# LaserBoardv1_0.net
KiCad netlist of a schematic drawn in EAGLE
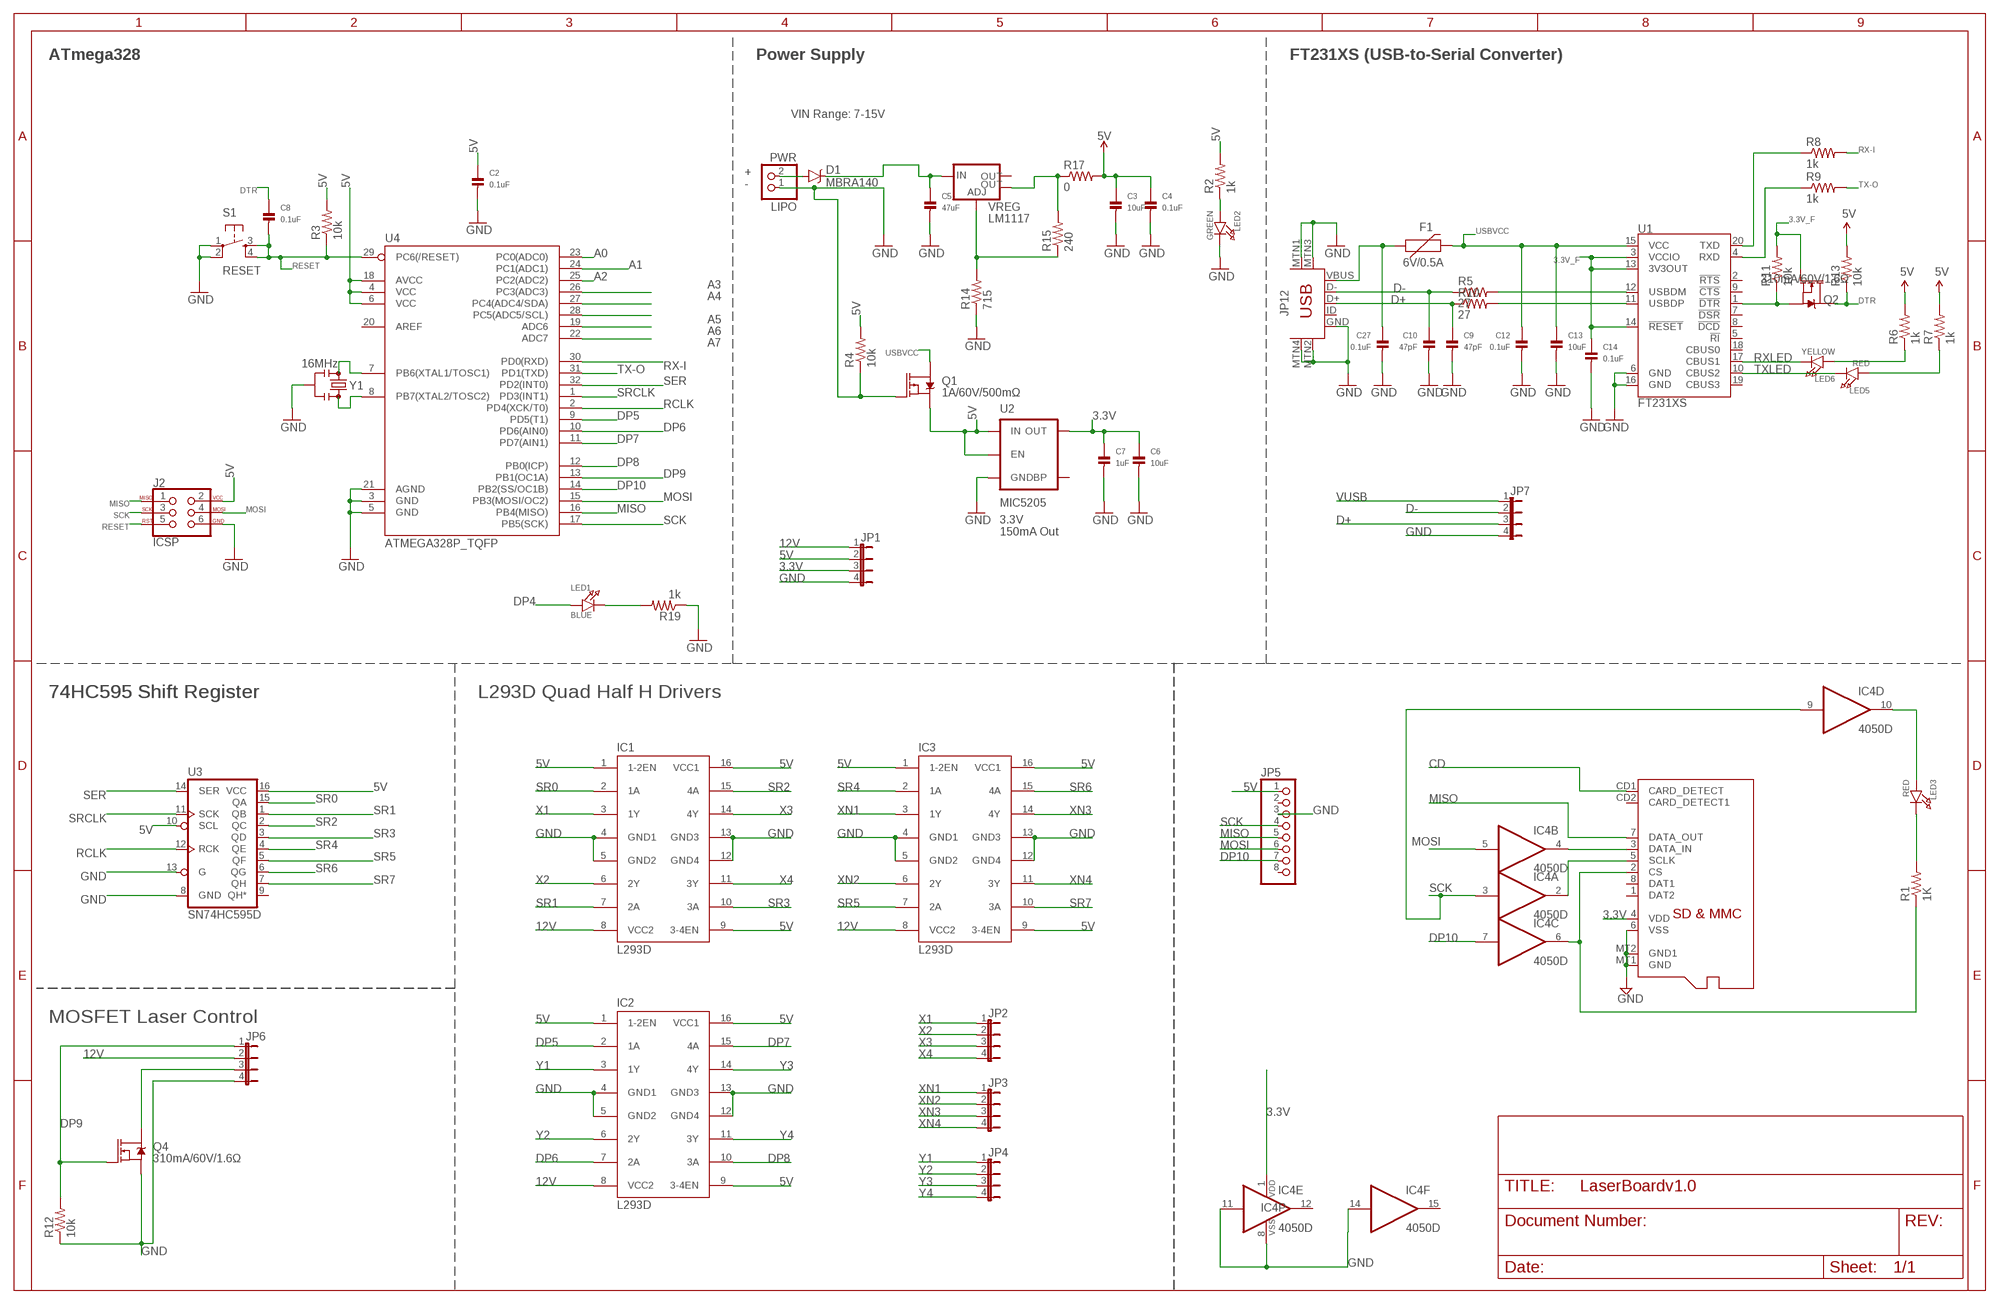
[diagram p0: schematic, sheet 1]

(export (version "E")
  (design (tool "Eeschema 10.0.6"))
  (components
    (comp (ref "C2")
      (value "0.1uF")
      (footprint "eagle-import:0805")
      (libsource (lib "eagle-import") (part "CAP_CERAMIC0805"))
    )
    (comp (ref "C3")
      (value "10uF")
      (footprint "eagle-import:0805")
      (libsource (lib "eagle-import") (part "CAP_CERAMIC0805"))
    )
    (comp (ref "C4")
      (value "0.1uF")
      (footprint "eagle-import:0805")
      (libsource (lib "eagle-import") (part "CAP_CERAMIC0805"))
    )
    (comp (ref "C5")
      (value "47uF")
      (footprint "eagle-import:0805")
      (libsource (lib "eagle-import") (part "CAP_CERAMIC0805"))
    )
    (comp (ref "C6")
      (value "10uF")
      (footprint "eagle-import:0805")
      (libsource (lib "eagle-import") (part "CAP_CERAMIC0805"))
    )
    (comp (ref "C7")
      (value "1uF")
      (footprint "eagle-import:0805")
      (libsource (lib "eagle-import") (part "CAP_CERAMIC0805"))
    )
    (comp (ref "C8")
      (value "0.1uF")
      (footprint "eagle-import:0805")
      (libsource (lib "eagle-import") (part "CAP_CERAMIC0805"))
    )
    (comp (ref "C9")
      (value "47pF")
      (footprint "eagle-import:0805")
      (libsource (lib "eagle-import") (part "CAP_CERAMIC0805"))
    )
    (comp (ref "C10")
      (value "47pF")
      (footprint "eagle-import:0805")
      (libsource (lib "eagle-import") (part "CAP_CERAMIC0805"))
    )
    (comp (ref "C12")
      (value "0.1uF")
      (footprint "eagle-import:0805")
      (libsource (lib "eagle-import") (part "CAP_CERAMIC0805"))
    )
    (comp (ref "C13")
      (value "10uF")
      (footprint "eagle-import:0805")
      (libsource (lib "eagle-import") (part "CAP_CERAMIC0805"))
    )
    (comp (ref "C14")
      (value "0.1uF")
      (footprint "eagle-import:0805")
      (libsource (lib "eagle-import") (part "CAP_CERAMIC0805"))
    )
    (comp (ref "C27")
      (value "0.1uF")
      (footprint "eagle-import:0805")
      (libsource (lib "eagle-import") (part "CAP_CERAMIC0805"))
    )
    (comp (ref "D1")
      (value "MBRA140")
      (footprint "eagle-import:SMA-DIODE")
      (libsource (lib "eagle-import") (part "MBRA140"))
    )
    (comp (ref "F1")
      (value "6V/0.5A")
      (footprint "eagle-import:1206")
      (libsource (lib "eagle-import") (part "PTC-HALF_AMP"))
    )
    (comp (ref "IC1")
      (value "L293D")
      (footprint "eagle-import:DIL16")
      (fields (field (name "MF") "STMicroelectronics"))
      (libsource (lib "eagle-import") (part "L293D"))
    )
    (comp (ref "IC2")
      (value "L293D")
      (footprint "eagle-import:DIL16")
      (fields (field (name "MF") "STMicroelectronics"))
      (libsource (lib "eagle-import") (part "L293D"))
    )
    (comp (ref "IC3")
      (value "L293D")
      (footprint "eagle-import:DIL16")
      (fields (field (name "MF") "STMicroelectronics"))
      (libsource (lib "eagle-import") (part "L293D"))
    )
    (comp (ref "IC4")
      (value "4050D")
      (footprint "eagle-import:SO16")
      (libsource (lib "eagle-import") (part "4050D"))
    )
    (comp (ref "J2")
      (value "ICSP")
      (footprint "eagle-import:2X3")
      (libsource (lib "eagle-import") (part "AVR_SPI_PROG_3X2PTH"))
    )
    (comp (ref "JP1")
      (value "JP4E")
      (footprint "eagle-import:JP4")
      (libsource (lib "eagle-import") (part "JP4E"))
    )
    (comp (ref "JP2")
      (value "JP4E")
      (footprint "eagle-import:JP4")
      (libsource (lib "eagle-import") (part "JP4E"))
    )
    (comp (ref "JP3")
      (value "JP4E")
      (footprint "eagle-import:JP4")
      (libsource (lib "eagle-import") (part "JP4E"))
    )
    (comp (ref "JP4")
      (value "JP4E")
      (footprint "eagle-import:JP4")
      (libsource (lib "eagle-import") (part "JP4E"))
    )
    (comp (ref "JP5")
      (value "PINHD-1X8BIG")
      (footprint "eagle-import:1X08-BIG")
      (libsource (lib "eagle-import") (part "PINHD-1X8BIG"))
    )
    (comp (ref "JP6")
      (value "JP4E")
      (footprint "eagle-import:JP4")
      (libsource (lib "eagle-import") (part "JP4E"))
    )
    (comp (ref "JP7")
      (value "JP4E")
      (footprint "eagle-import:JP4")
      (libsource (lib "eagle-import") (part "JP4E"))
    )
    (comp (ref "JP12")
      (value "USB-MINIB-5PIN")
      (footprint "eagle-import:USB-MINIB")
      (libsource (lib "eagle-import") (part "USB-MINIB-5PIN"))
    )
    (comp (ref "LED1")
      (value "BLUE")
      (footprint "eagle-import:CHIPLED_0805")
      (libsource (lib "eagle-import") (part "LED0805"))
    )
    (comp (ref "LED2")
      (value "GREEN")
      (footprint "eagle-import:CHIPLED_0805")
      (libsource (lib "eagle-import") (part "LED0805"))
    )
    (comp (ref "LED3")
      (value "RED")
      (footprint "eagle-import:CHIPLED_0805")
      (libsource (lib "eagle-import") (part "LED0805"))
    )
    (comp (ref "LED5")
      (value "RED")
      (footprint "eagle-import:CHIPLED_0805")
      (libsource (lib "eagle-import") (part "LED0805"))
    )
    (comp (ref "LED6")
      (value "YELLOW")
      (footprint "eagle-import:CHIPLED_0805")
      (libsource (lib "eagle-import") (part "LED0805"))
    )
    (comp (ref "PWR")
      (value "LIPO")
      (footprint "eagle-import:JST-PH-2-THM-RA")
      (libsource (lib "eagle-import") (part "JST_2PIN-THM-RA"))
    )
    (comp (ref "Q1")
      (value "1A/60V/500mΩ")
      (footprint "eagle-import:SOT23-3")
      (libsource (lib "eagle-import") (part "MOSFET-PCH-ZXMP6A13F"))
    )
    (comp (ref "Q2")
      (value "310mA/60V/1.6Ω")
      (footprint "eagle-import:SOT323")
      (libsource (lib "eagle-import") (part "MOSFET-NCH-2N7002PW"))
    )
    (comp (ref "Q4")
      (value "310mA/60V/1.6Ω")
      (footprint "eagle-import:SOT323")
      (libsource (lib "eagle-import") (part "SparkFun-DiscreteSemi_514_MOSFET-NCH-2N7002PW"))
    )
    (comp (ref "R1")
      (value "1K")
      (footprint "eagle-import:R0805")
      (libsource (lib "eagle-import") (part "R-US_R0805"))
    )
    (comp (ref "R2")
      (value "1k")
      (footprint "eagle-import:R0805")
      (libsource (lib "eagle-import") (part "R-US_R0805"))
    )
    (comp (ref "R3")
      (value "10k")
      (footprint "eagle-import:R0805")
      (libsource (lib "eagle-import") (part "R-US_R0805"))
    )
    (comp (ref "R4")
      (value "10k")
      (footprint "eagle-import:R0805")
      (libsource (lib "eagle-import") (part "R-US_R0805"))
    )
    (comp (ref "R5")
      (value "27")
      (footprint "eagle-import:R0805")
      (libsource (lib "eagle-import") (part "R-US_R0805"))
    )
    (comp (ref "R6")
      (value "1k")
      (footprint "eagle-import:R0805")
      (libsource (lib "eagle-import") (part "R-US_R0805"))
    )
    (comp (ref "R7")
      (value "1k")
      (footprint "eagle-import:R0805")
      (libsource (lib "eagle-import") (part "R-US_R0805"))
    )
    (comp (ref "R8")
      (value "1k")
      (footprint "eagle-import:R0805")
      (libsource (lib "eagle-import") (part "R-US_R0805"))
    )
    (comp (ref "R9")
      (value "1k")
      (footprint "eagle-import:R0805")
      (libsource (lib "eagle-import") (part "R-US_R0805"))
    )
    (comp (ref "R10")
      (value "27")
      (footprint "eagle-import:R0805")
      (libsource (lib "eagle-import") (part "R-US_R0805"))
    )
    (comp (ref "R11")
      (value "10k")
      (footprint "eagle-import:R0805")
      (libsource (lib "eagle-import") (part "R-US_R0805"))
    )
    (comp (ref "R12")
      (value "10k")
      (footprint "eagle-import:R0805")
      (libsource (lib "eagle-import") (part "R-US_R0805"))
    )
    (comp (ref "R13")
      (value "10k")
      (footprint "eagle-import:R0805")
      (libsource (lib "eagle-import") (part "R-US_R0805"))
    )
    (comp (ref "R14")
      (value "715")
      (footprint "eagle-import:R0805")
      (libsource (lib "eagle-import") (part "R-US_R0805"))
    )
    (comp (ref "R15")
      (value "240")
      (footprint "eagle-import:R0805")
      (libsource (lib "eagle-import") (part "R-US_R0805"))
    )
    (comp (ref "R17")
      (value "0")
      (footprint "eagle-import:R0805")
      (libsource (lib "eagle-import") (part "R-US_R0805"))
    )
    (comp (ref "R19")
      (value "1k")
      (footprint "eagle-import:R0805")
      (libsource (lib "eagle-import") (part "R-US_R0805"))
    )
    (comp (ref "S1")
      (value "RESET")
      (footprint "eagle-import:TACTILE_SWITCH_SMD_4.6X2.8MM")
      (libsource (lib "eagle-import") (part "SWITCH_SPST_4_PINRECT"))
    )
    (comp (ref "U1")
      (value "FT231XS")
      (footprint "eagle-import:SSOP20_L")
      (libsource (lib "eagle-import") (part "FT231XS"))
    )
    (comp (ref "U2")
      (value "MIC5205")
      (footprint "eagle-import:SOT23-5")
      (libsource (lib "eagle-import") (part "MIC52053.3V"))
    )
    (comp (ref "U3")
      (value "SN74HC595D")
      (footprint "eagle-import:SO16")
      (libsource (lib "eagle-import") (part "74595DHC"))
    )
    (comp (ref "U4")
      (value "ATMEGA328P_TQFP")
      (footprint "eagle-import:TQFP32-08")
      (libsource (lib "eagle-import") (part "ATMEGA328P_TQFP"))
    )
    (comp (ref "VREG")
      (value "LM1117")
      (footprint "eagle-import:SOT223")
      (libsource (lib "eagle-import") (part "V_REG_LM1117SOT223"))
    )
    (comp (ref "X1")
      (value "MICROSD")
      (footprint "eagle-import:MICROSD")
      (libsource (lib "eagle-import") (part "MICROSD"))
    )
    (comp (ref "Y1")
      (value "16MHz")
      (footprint "eagle-import:RESONATOR-SMD-3.2X1.3")
      (libsource (lib "eagle-import") (part "RESONATOR-16MHZSMD_3.2X1.3"))
    )
  )
  (nets
    (net (code "1") (name "/3.3V") (class "Default")
      (node (ref "C6") (pin "1") (pinfunction "P$1_1") (pintype "passive"))
      (node (ref "C7") (pin "1") (pinfunction "P$1_1") (pintype "passive"))
      (node (ref "IC4") (pin "1") (pinfunction "VDD_1") (pintype "power_in"))
      (node (ref "JP1") (pin "3") (pinfunction "3_3") (pintype "passive"))
      (node (ref "U2") (pin "5") (pinfunction "OUT_5") (pintype "passive"))
      (node (ref "X1") (pin "4") (pinfunction "VDD_4") (pintype "power_in"))
    )
    (net (code "2") (name "/12V") (class "Default")
      (node (ref "C5") (pin "1") (pinfunction "P$1_1") (pintype "passive"))
      (node (ref "D1") (pin "C") (pinfunction "C_C") (pintype "passive"))
      (node (ref "IC1") (pin "8") (pinfunction "VCC2_8") (pintype "power_in"))
      (node (ref "IC2") (pin "8") (pinfunction "VCC2_8") (pintype "power_in"))
      (node (ref "IC3") (pin "8") (pinfunction "VCC2_8") (pintype "power_in"))
      (node (ref "JP1") (pin "1") (pinfunction "1_1") (pintype "passive"))
      (node (ref "JP6") (pin "2") (pinfunction "2_2") (pintype "passive"))
      (node (ref "VREG") (pin "3") (pinfunction "IN_3") (pintype "input"))
    )
    (net (code "3") (name "/CD") (class "Default")
      (node (ref "X1") (pin "CD1") (pinfunction "CARD_DETECT_CD1") (pintype "passive"))
    )
    (net (code "4") (name "/D+") (class "Default")
      (node (ref "C9") (pin "1") (pinfunction "P$1_1") (pintype "passive"))
      (node (ref "JP12") (pin "D+") (pinfunction "D+_D+") (pintype "bidirectional"))
      (node (ref "JP7") (pin "3") (pinfunction "3_3") (pintype "passive"))
      (node (ref "R10") (pin "1") (pinfunction "1_1") (pintype "passive"))
    )
    (net (code "5") (name "/D-") (class "Default")
      (node (ref "C10") (pin "1") (pinfunction "P$1_1") (pintype "passive"))
      (node (ref "JP12") (pin "D-") (pinfunction "D-_D-") (pintype "bidirectional"))
      (node (ref "JP7") (pin "2") (pinfunction "2_2") (pintype "passive"))
      (node (ref "R5") (pin "1") (pinfunction "1_1") (pintype "passive"))
    )
    (net (code "6") (name "/RXLED") (class "Default")
      (node (ref "LED6") (pin "C") (pinfunction "C_C") (pintype "passive"))
      (node (ref "U1") (pin "17") (pinfunction "CBUS1_17") (pintype "bidirectional"))
    )
    (net (code "7") (name "/TXLED") (class "Default")
      (node (ref "LED5") (pin "C") (pinfunction "C_C") (pintype "passive"))
      (node (ref "U1") (pin "10") (pinfunction "CBUS2_10") (pintype "bidirectional"))
    )
    (net (code "8") (name "/VUSB") (class "Default")
      (node (ref "C27") (pin "1") (pinfunction "P$1_1") (pintype "passive"))
      (node (ref "F1") (pin "1") (pinfunction "1_1") (pintype "bidirectional"))
      (node (ref "JP12") (pin "VBUS") (pinfunction "VBUS_VBUS") (pintype "bidirectional"))
      (node (ref "JP7") (pin "1") (pinfunction "1_1") (pintype "passive"))
    )
    (net (code "9") (name "/X1") (class "Default")
      (node (ref "IC1") (pin "3") (pinfunction "1Y_3") (pintype "output"))
      (node (ref "JP2") (pin "1") (pinfunction "1_1") (pintype "passive"))
    )
    (net (code "10") (name "/X2") (class "Default")
      (node (ref "IC1") (pin "6") (pinfunction "2Y_6") (pintype "output"))
      (node (ref "JP2") (pin "2") (pinfunction "2_2") (pintype "passive"))
    )
    (net (code "11") (name "/X3") (class "Default")
      (node (ref "IC1") (pin "14") (pinfunction "4Y_14") (pintype "output"))
      (node (ref "JP2") (pin "3") (pinfunction "3_3") (pintype "passive"))
    )
    (net (code "12") (name "/X4") (class "Default")
      (node (ref "IC1") (pin "11") (pinfunction "3Y_11") (pintype "output"))
      (node (ref "JP2") (pin "4") (pinfunction "4_4") (pintype "passive"))
    )
    (net (code "13") (name "/XN1") (class "Default")
      (node (ref "IC3") (pin "3") (pinfunction "1Y_3") (pintype "output"))
      (node (ref "JP3") (pin "1") (pinfunction "1_1") (pintype "passive"))
    )
    (net (code "14") (name "/XN2") (class "Default")
      (node (ref "IC3") (pin "6") (pinfunction "2Y_6") (pintype "output"))
      (node (ref "JP3") (pin "2") (pinfunction "2_2") (pintype "passive"))
    )
    (net (code "15") (name "/XN3") (class "Default")
      (node (ref "IC3") (pin "14") (pinfunction "4Y_14") (pintype "output"))
      (node (ref "JP3") (pin "3") (pinfunction "3_3") (pintype "passive"))
    )
    (net (code "16") (name "/XN4") (class "Default")
      (node (ref "IC3") (pin "11") (pinfunction "3Y_11") (pintype "output"))
      (node (ref "JP3") (pin "4") (pinfunction "4_4") (pintype "passive"))
    )
    (net (code "17") (name "/Y1") (class "Default")
      (node (ref "IC2") (pin "3") (pinfunction "1Y_3") (pintype "output"))
      (node (ref "JP4") (pin "1") (pinfunction "1_1") (pintype "passive"))
    )
    (net (code "18") (name "/Y2") (class "Default")
      (node (ref "IC2") (pin "6") (pinfunction "2Y_6") (pintype "output"))
      (node (ref "JP4") (pin "2") (pinfunction "2_2") (pintype "passive"))
    )
    (net (code "19") (name "/Y3") (class "Default")
      (node (ref "IC2") (pin "14") (pinfunction "4Y_14") (pintype "output"))
      (node (ref "JP4") (pin "3") (pinfunction "3_3") (pintype "passive"))
    )
    (net (code "20") (name "/Y4") (class "Default")
      (node (ref "IC2") (pin "11") (pinfunction "3Y_11") (pintype "output"))
      (node (ref "JP4") (pin "4") (pinfunction "4_4") (pintype "passive"))
    )
    (net (code "21") (name "3.3V_F") (class "Default")
      (node (ref "C14") (pin "1") (pinfunction "P$1_1") (pintype "passive"))
      (node (ref "Q2") (pin "1") (pinfunction "G_1") (pintype "bidirectional"))
      (node (ref "R11") (pin "2") (pinfunction "2_2") (pintype "passive"))
      (node (ref "U1") (pin "13") (pinfunction "3V3OUT_13") (pintype "bidirectional"))
      (node (ref "U1") (pin "14") (pinfunction "~{RESET}_14") (pintype "bidirectional"))
      (node (ref "U1") (pin "3") (pinfunction "VCCIO_3") (pintype "bidirectional"))
    )
    (net (code "22") (name "5V") (class "Default")
      (node (ref "C2") (pin "1") (pinfunction "P$1_1") (pintype "passive"))
      (node (ref "C3") (pin "1") (pinfunction "P$1_1") (pintype "passive"))
      (node (ref "C4") (pin "1") (pinfunction "P$1_1") (pintype "passive"))
      (node (ref "IC1") (pin "1") (pinfunction "1-2EN_1") (pintype "input"))
      (node (ref "IC1") (pin "16") (pinfunction "VCC1_16") (pintype "power_in"))
      (node (ref "IC1") (pin "9") (pinfunction "3-4EN_9") (pintype "input"))
      (node (ref "IC2") (pin "1") (pinfunction "1-2EN_1") (pintype "input"))
      (node (ref "IC2") (pin "16") (pinfunction "VCC1_16") (pintype "power_in"))
      (node (ref "IC2") (pin "9") (pinfunction "3-4EN_9") (pintype "input"))
      (node (ref "IC3") (pin "1") (pinfunction "1-2EN_1") (pintype "input"))
      (node (ref "IC3") (pin "16") (pinfunction "VCC1_16") (pintype "power_in"))
      (node (ref "IC3") (pin "9") (pinfunction "3-4EN_9") (pintype "input"))
      (node (ref "J2") (pin "2") (pinfunction "2_2") (pintype "passive"))
      (node (ref "JP1") (pin "2") (pinfunction "2_2") (pintype "passive"))
      (node (ref "JP5") (pin "1") (pinfunction "1_1") (pintype "passive"))
      (node (ref "Q1") (pin "2") (pinfunction "S_2") (pintype "bidirectional"))
      (node (ref "R13") (pin "2") (pinfunction "2_2") (pintype "passive"))
      (node (ref "R17") (pin "2") (pinfunction "2_2") (pintype "passive"))
      (node (ref "R2") (pin "2") (pinfunction "2_2") (pintype "passive"))
      (node (ref "R3") (pin "2") (pinfunction "2_2") (pintype "passive"))
      (node (ref "R4") (pin "2") (pinfunction "2_2") (pintype "passive"))
      (node (ref "R6") (pin "2") (pinfunction "2_2") (pintype "passive"))
      (node (ref "R7") (pin "2") (pinfunction "2_2") (pintype "passive"))
      (node (ref "U2") (pin "1") (pinfunction "IN_1") (pintype "input"))
      (node (ref "U2") (pin "3") (pinfunction "EN_3") (pintype "input"))
      (node (ref "U3") (pin "10") (pinfunction "SCL_10") (pintype "input"))
      (node (ref "U3") (pin "16") (pinfunction "VCC_16") (pintype "power_in"))
      (node (ref "U4") (pin "18") (pinfunction "AVCC_18") (pintype "bidirectional"))
      (node (ref "U4") (pin "4") (pinfunction "VCC_4") (pintype "bidirectional"))
      (node (ref "U4") (pin "6") (pinfunction "VCC_6") (pintype "bidirectional"))
    )
    (net (code "23") (name "A0") (class "Default")
      (node (ref "U4") (pin "23") (pinfunction "PC0(ADC0)_23") (pintype "bidirectional"))
    )
    (net (code "24") (name "A1") (class "Default")
      (node (ref "U4") (pin "24") (pinfunction "PC1(ADC1)_24") (pintype "bidirectional"))
    )
    (net (code "25") (name "A2") (class "Default")
      (node (ref "U4") (pin "25") (pinfunction "PC2(ADC2)_25") (pintype "bidirectional"))
    )
    (net (code "26") (name "DP4") (class "Default")
      (node (ref "LED1") (pin "A") (pinfunction "A_A") (pintype "passive"))
    )
    (net (code "27") (name "DP5") (class "Default")
      (node (ref "IC2") (pin "2") (pinfunction "1A_2") (pintype "input"))
      (node (ref "U4") (pin "9") (pinfunction "PD5(T1)_9") (pintype "bidirectional"))
    )
    (net (code "28") (name "DP6") (class "Default")
      (node (ref "IC2") (pin "7") (pinfunction "2A_7") (pintype "input"))
      (node (ref "U4") (pin "10") (pinfunction "PD6(AIN0)_10") (pintype "bidirectional"))
    )
    (net (code "29") (name "DP7") (class "Default")
      (node (ref "IC2") (pin "15") (pinfunction "4A_15") (pintype "input"))
      (node (ref "U4") (pin "11") (pinfunction "PD7(AIN1)_11") (pintype "bidirectional"))
    )
    (net (code "30") (name "DP8") (class "Default")
      (node (ref "IC2") (pin "10") (pinfunction "3A_10") (pintype "input"))
      (node (ref "U4") (pin "12") (pinfunction "PB0(ICP)_12") (pintype "bidirectional"))
    )
    (net (code "31") (name "DP9") (class "Default")
      (node (ref "JP6") (pin "1") (pinfunction "1_1") (pintype "passive"))
      (node (ref "Q4") (pin "1") (pinfunction "G_1") (pintype "bidirectional"))
      (node (ref "R12") (pin "2") (pinfunction "2_2") (pintype "passive"))
      (node (ref "U4") (pin "13") (pinfunction "PB1(OC1A)_13") (pintype "bidirectional"))
    )
    (net (code "32") (name "DP10") (class "Default")
      (node (ref "IC4") (pin "7") (pinfunction "I_7") (pintype "input"))
      (node (ref "JP5") (pin "7") (pinfunction "7_7") (pintype "passive"))
      (node (ref "U4") (pin "14") (pinfunction "PB2(SS/OC1B)_14") (pintype "bidirectional"))
    )
    (net (code "33") (name "DTR") (class "Default")
      (node (ref "C8") (pin "1") (pinfunction "P$1_1") (pintype "passive"))
      (node (ref "Q2") (pin "3") (pinfunction "D_3") (pintype "bidirectional"))
      (node (ref "R13") (pin "1") (pinfunction "1_1") (pintype "passive"))
    )
    (net (code "34") (name "GND") (class "Default")
      (node (ref "C10") (pin "2") (pinfunction "P$2_2") (pintype "passive"))
      (node (ref "C12") (pin "2") (pinfunction "P$2_2") (pintype "passive"))
      (node (ref "C13") (pin "2") (pinfunction "P$2_2") (pintype "passive"))
      (node (ref "C14") (pin "2") (pinfunction "P$2_2") (pintype "passive"))
      (node (ref "C2") (pin "2") (pinfunction "P$2_2") (pintype "passive"))
      (node (ref "C27") (pin "2") (pinfunction "P$2_2") (pintype "passive"))
      (node (ref "C3") (pin "2") (pinfunction "P$2_2") (pintype "passive"))
      (node (ref "C4") (pin "2") (pinfunction "P$2_2") (pintype "passive"))
      (node (ref "C5") (pin "2") (pinfunction "P$2_2") (pintype "passive"))
      (node (ref "C6") (pin "2") (pinfunction "P$2_2") (pintype "passive"))
      (node (ref "C7") (pin "2") (pinfunction "P$2_2") (pintype "passive"))
      (node (ref "C9") (pin "2") (pinfunction "P$2_2") (pintype "passive"))
      (node (ref "IC1") (pin "12") (pinfunction "GND4_12") (pintype "power_in"))
      (node (ref "IC1") (pin "13") (pinfunction "GND3_13") (pintype "power_in"))
      (node (ref "IC1") (pin "4") (pinfunction "GND1_4") (pintype "power_in"))
      (node (ref "IC1") (pin "5") (pinfunction "GND2_5") (pintype "power_in"))
      (node (ref "IC2") (pin "12") (pinfunction "GND4_12") (pintype "power_in"))
      (node (ref "IC2") (pin "13") (pinfunction "GND3_13") (pintype "power_in"))
      (node (ref "IC2") (pin "4") (pinfunction "GND1_4") (pintype "power_in"))
      (node (ref "IC2") (pin "5") (pinfunction "GND2_5") (pintype "power_in"))
      (node (ref "IC3") (pin "12") (pinfunction "GND4_12") (pintype "power_in"))
      (node (ref "IC3") (pin "13") (pinfunction "GND3_13") (pintype "power_in"))
      (node (ref "IC3") (pin "4") (pinfunction "GND1_4") (pintype "power_in"))
      (node (ref "IC3") (pin "5") (pinfunction "GND2_5") (pintype "power_in"))
      (node (ref "IC4") (pin "11") (pinfunction "I_11") (pintype "input"))
      (node (ref "IC4") (pin "14") (pinfunction "I_14") (pintype "input"))
      (node (ref "IC4") (pin "8") (pinfunction "VSS_8") (pintype "power_in"))
      (node (ref "J2") (pin "6") (pinfunction "6_6") (pintype "passive"))
      (node (ref "JP1") (pin "4") (pinfunction "4_4") (pintype "passive"))
      (node (ref "JP12") (pin "GND") (pinfunction "GND_GND") (pintype "bidirectional"))
      (node (ref "JP12") (pin "MTN1") (pinfunction "MTN2_MTN1") (pintype "bidirectional"))
      (node (ref "JP12") (pin "MTN2") (pinfunction "MTN3_MTN2") (pintype "bidirectional"))
      (node (ref "JP12") (pin "MTN3") (pinfunction "MTN1_MTN3") (pintype "bidirectional"))
      (node (ref "JP12") (pin "MTN4") (pinfunction "MTN4_MTN4") (pintype "bidirectional"))
      (node (ref "JP5") (pin "3") (pinfunction "3_3") (pintype "passive"))
      (node (ref "JP6") (pin "4") (pinfunction "4_4") (pintype "passive"))
      (node (ref "JP7") (pin "4") (pinfunction "4_4") (pintype "passive"))
      (node (ref "LED2") (pin "C") (pinfunction "C_C") (pintype "passive"))
      (node (ref "PWR") (pin "1") (pinfunction "2_1") (pintype "passive"))
      (node (ref "Q1") (pin "1") (pinfunction "G_1") (pintype "bidirectional"))
      (node (ref "Q4") (pin "2") (pinfunction "S_2") (pintype "bidirectional"))
      (node (ref "R12") (pin "1") (pinfunction "1_1") (pintype "passive"))
      (node (ref "R14") (pin "1") (pinfunction "1_1") (pintype "passive"))
      (node (ref "R19") (pin "1") (pinfunction "1_1") (pintype "passive"))
      (node (ref "R4") (pin "1") (pinfunction "1_1") (pintype "passive"))
      (node (ref "S1") (pin "1") (pinfunction "1_1") (pintype "passive"))
      (node (ref "S1") (pin "2") (pinfunction "2_2") (pintype "passive"))
      (node (ref "U1") (pin "16") (pinfunction "GND_16") (pintype "bidirectional"))
      (node (ref "U1") (pin "6") (pinfunction "GND_6") (pintype "bidirectional"))
      (node (ref "U2") (pin "2") (pinfunction "GND_2") (pintype "input"))
      (node (ref "U3") (pin "13") (pinfunction "G_13") (pintype "input"))
      (node (ref "U3") (pin "8") (pinfunction "GND_8") (pintype "power_in"))
      (node (ref "U4") (pin "21") (pinfunction "AGND_21") (pintype "bidirectional"))
      (node (ref "U4") (pin "3") (pinfunction "GND_3") (pintype "bidirectional"))
      (node (ref "U4") (pin "5") (pinfunction "GND_5") (pintype "bidirectional"))
      (node (ref "X1") (pin "6") (pinfunction "VSS_6") (pintype "power_in"))
      (node (ref "X1") (pin "MT1") (pinfunction "GND_MT1") (pintype "power_in"))
      (node (ref "X1") (pin "MT2") (pinfunction "GND1_MT2") (pintype "power_in"))
      (node (ref "Y1") (pin "2") (pinfunction "2_2") (pintype "passive"))
    )
    (net (code "35") (name "MISO") (class "Default")
      (node (ref "J2") (pin "1") (pinfunction "1_1") (pintype "passive"))
      (node (ref "JP5") (pin "5") (pinfunction "5_5") (pintype "passive"))
      (node (ref "U4") (pin "16") (pinfunction "PB4(MISO)_16") (pintype "bidirectional"))
      (node (ref "X1") (pin "7") (pinfunction "DATA_OUT_7") (pintype "output"))
    )
    (net (code "36") (name "MOSI") (class "Default")
      (node (ref "IC4") (pin "5") (pinfunction "I_5") (pintype "input"))
      (node (ref "J2") (pin "4") (pinfunction "4_4") (pintype "passive"))
      (node (ref "JP5") (pin "6") (pinfunction "6_6") (pintype "passive"))
      (node (ref "U4") (pin "15") (pinfunction "PB3(MOSI/OC2)_15") (pintype "bidirectional"))
    )
    (net (code "37") (name "Net-(IC4A-O)") (class "Default")
      (node (ref "IC4") (pin "2") (pinfunction "O_2") (pintype "output"))
      (node (ref "X1") (pin "5") (pinfunction "SCLK_5") (pintype "input"))
    )
    (net (code "38") (name "Net-(IC4B-O)") (class "Default")
      (node (ref "IC4") (pin "4") (pinfunction "O_4") (pintype "output"))
      (node (ref "X1") (pin "3") (pinfunction "DATA_IN_3") (pintype "input"))
    )
    (net (code "39") (name "Net-(IC4C-O)") (class "Default")
      (node (ref "IC4") (pin "6") (pinfunction "O_6") (pintype "output"))
      (node (ref "R1") (pin "1") (pinfunction "1_1") (pintype "passive"))
      (node (ref "X1") (pin "2") (pinfunction "CS_2") (pintype "input"))
    )
    (net (code "40") (name "Net-(IC4D-O)") (class "Default")
      (node (ref "IC4") (pin "10") (pinfunction "O_10") (pintype "output"))
      (node (ref "LED3") (pin "A") (pinfunction "A_A") (pintype "passive"))
    )
    (net (code "41") (name "Net-(LED1-PadC)") (class "Default")
      (node (ref "LED1") (pin "C") (pinfunction "C_C") (pintype "passive"))
      (node (ref "R19") (pin "2") (pinfunction "2_2") (pintype "passive"))
    )
    (net (code "42") (name "Net-(LED2-PadA)") (class "Default")
      (node (ref "LED2") (pin "A") (pinfunction "A_A") (pintype "passive"))
      (node (ref "R2") (pin "1") (pinfunction "1_1") (pintype "passive"))
    )
    (net (code "43") (name "Net-(LED3-PadC)") (class "Default")
      (node (ref "LED3") (pin "C") (pinfunction "C_C") (pintype "passive"))
      (node (ref "R1") (pin "2") (pinfunction "2_2") (pintype "passive"))
    )
    (net (code "44") (name "Net-(LED5-PadA)") (class "Default")
      (node (ref "LED5") (pin "A") (pinfunction "A_A") (pintype "passive"))
      (node (ref "R7") (pin "1") (pinfunction "1_1") (pintype "passive"))
    )
    (net (code "45") (name "Net-(LED6-PadA)") (class "Default")
      (node (ref "LED6") (pin "A") (pinfunction "A_A") (pintype "passive"))
      (node (ref "R6") (pin "1") (pinfunction "1_1") (pintype "passive"))
    )
    (net (code "46") (name "Net-(PWR-1)") (class "Default")
      (node (ref "D1") (pin "A") (pinfunction "A_A") (pintype "passive"))
      (node (ref "PWR") (pin "2") (pinfunction "1_2") (pintype "passive"))
    )
    (net (code "47") (name "Net-(Q2-S)") (class "Default")
      (node (ref "Q2") (pin "2") (pinfunction "S_2") (pintype "bidirectional"))
      (node (ref "R11") (pin "1") (pinfunction "1_1") (pintype "passive"))
      (node (ref "U1") (pin "1") (pinfunction "~{DTR}_1") (pintype "bidirectional"))
    )
    (net (code "48") (name "Net-(Q4-D)") (class "Default")
      (node (ref "JP6") (pin "3") (pinfunction "3_3") (pintype "passive"))
      (node (ref "Q4") (pin "3") (pinfunction "D_3") (pintype "bidirectional"))
    )
    (net (code "49") (name "Net-(R15-Pad2)") (class "Default")
      (node (ref "R15") (pin "2") (pinfunction "2_2") (pintype "passive"))
      (node (ref "R17") (pin "1") (pinfunction "1_1") (pintype "passive"))
      (node (ref "VREG") (pin "4") (pinfunction "OUT_4") (pintype "output"))
    )
    (net (code "50") (name "Net-(U1-RXD)") (class "Default")
      (node (ref "R9") (pin "1") (pinfunction "1_1") (pintype "passive"))
      (node (ref "U1") (pin "4") (pinfunction "RXD_4") (pintype "bidirectional"))
    )
    (net (code "51") (name "Net-(U1-TXD)") (class "Default")
      (node (ref "R8") (pin "1") (pinfunction "1_1") (pintype "passive"))
      (node (ref "U1") (pin "20") (pinfunction "TXD_20") (pintype "bidirectional"))
    )
    (net (code "52") (name "Net-(U1-USBDM)") (class "Default")
      (node (ref "R5") (pin "2") (pinfunction "2_2") (pintype "passive"))
      (node (ref "U1") (pin "12") (pinfunction "USBDM_12") (pintype "bidirectional"))
    )
    (net (code "53") (name "Net-(U1-USBDP)") (class "Default")
      (node (ref "R10") (pin "2") (pinfunction "2_2") (pintype "passive"))
      (node (ref "U1") (pin "11") (pinfunction "USBDP_11") (pintype "bidirectional"))
    )
    (net (code "54") (name "Net-(U4-PB6(XTAL1{slash}TOSC1))") (class "Default")
      (node (ref "U4") (pin "7") (pinfunction "PB6(XTAL1/TOSC1)_7") (pintype "bidirectional"))
      (node (ref "Y1") (pin "1") (pinfunction "1_1") (pintype "passive"))
    )
    (net (code "55") (name "Net-(U4-PB7(XTAL2{slash}TOSC2))") (class "Default")
      (node (ref "U4") (pin "8") (pinfunction "PB7(XTAL2/TOSC2)_8") (pintype "bidirectional"))
      (node (ref "Y1") (pin "3") (pinfunction "3_3") (pintype "passive"))
    )
    (net (code "56") (name "Net-(VREG-ADJ)") (class "Default")
      (node (ref "R14") (pin "2") (pinfunction "2_2") (pintype "passive"))
      (node (ref "R15") (pin "1") (pinfunction "1_1") (pintype "passive"))
      (node (ref "VREG") (pin "1") (pinfunction "ADJ_1") (pintype "input"))
    )
    (net (code "57") (name "RCLK") (class "Default")
      (node (ref "U3") (pin "12") (pinfunction "RCK_12") (pintype "input"))
      (node (ref "U4") (pin "2") (pinfunction "PD4(XCK/T0)_2") (pintype "bidirectional"))
    )
    (net (code "58") (name "RESET") (class "Default")
      (node (ref "C8") (pin "2") (pinfunction "P$2_2") (pintype "passive"))
      (node (ref "J2") (pin "5") (pinfunction "5_5") (pintype "passive"))
      (node (ref "R3") (pin "1") (pinfunction "1_1") (pintype "passive"))
      (node (ref "S1") (pin "3") (pinfunction "3_3") (pintype "passive"))
      (node (ref "S1") (pin "4") (pinfunction "4_4") (pintype "passive"))
      (node (ref "U4") (pin "29") (pinfunction "PC6(/RESET)_29") (pintype "bidirectional"))
    )
    (net (code "59") (name "RX-I") (class "Default")
      (node (ref "R8") (pin "2") (pinfunction "2_2") (pintype "passive"))
      (node (ref "U4") (pin "30") (pinfunction "PD0(RXD)_30") (pintype "bidirectional"))
    )
    (net (code "60") (name "SCK") (class "Default")
      (node (ref "IC4") (pin "3") (pinfunction "I_3") (pintype "input"))
      (node (ref "IC4") (pin "9") (pinfunction "I_9") (pintype "input"))
      (node (ref "J2") (pin "3") (pinfunction "3_3") (pintype "passive"))
      (node (ref "JP5") (pin "4") (pinfunction "4_4") (pintype "passive"))
      (node (ref "U4") (pin "17") (pinfunction "PB5(SCK)_17") (pintype "bidirectional"))
    )
    (net (code "61") (name "SER") (class "Default")
      (node (ref "U3") (pin "14") (pinfunction "SER_14") (pintype "input"))
      (node (ref "U4") (pin "32") (pinfunction "PD2(INT0)_32") (pintype "bidirectional"))
    )
    (net (code "62") (name "SR0") (class "Default")
      (node (ref "IC1") (pin "2") (pinfunction "1A_2") (pintype "input"))
      (node (ref "U3") (pin "15") (pinfunction "QA_15") (pintype "tri_state"))
    )
    (net (code "63") (name "SR1") (class "Default")
      (node (ref "IC1") (pin "7") (pinfunction "2A_7") (pintype "input"))
      (node (ref "U3") (pin "1") (pinfunction "QB_1") (pintype "tri_state"))
    )
    (net (code "64") (name "SR2") (class "Default")
      (node (ref "IC1") (pin "15") (pinfunction "4A_15") (pintype "input"))
      (node (ref "U3") (pin "2") (pinfunction "QC_2") (pintype "tri_state"))
    )
    (net (code "65") (name "SR3") (class "Default")
      (node (ref "IC1") (pin "10") (pinfunction "3A_10") (pintype "input"))
      (node (ref "U3") (pin "3") (pinfunction "QD_3") (pintype "tri_state"))
    )
    (net (code "66") (name "SR4") (class "Default")
      (node (ref "IC3") (pin "2") (pinfunction "1A_2") (pintype "input"))
      (node (ref "U3") (pin "4") (pinfunction "QE_4") (pintype "tri_state"))
    )
    (net (code "67") (name "SR5") (class "Default")
      (node (ref "IC3") (pin "7") (pinfunction "2A_7") (pintype "input"))
      (node (ref "U3") (pin "5") (pinfunction "QF_5") (pintype "tri_state"))
    )
    (net (code "68") (name "SR6") (class "Default")
      (node (ref "IC3") (pin "15") (pinfunction "4A_15") (pintype "input"))
      (node (ref "U3") (pin "6") (pinfunction "QG_6") (pintype "tri_state"))
    )
    (net (code "69") (name "SR7") (class "Default")
      (node (ref "IC3") (pin "10") (pinfunction "3A_10") (pintype "input"))
      (node (ref "U3") (pin "7") (pinfunction "QH_7") (pintype "tri_state"))
    )
    (net (code "70") (name "SRCLK") (class "Default")
      (node (ref "U3") (pin "11") (pinfunction "SCK_11") (pintype "input"))
      (node (ref "U4") (pin "1") (pinfunction "PD3(INT1)_1") (pintype "bidirectional"))
    )
    (net (code "71") (name "TX-O") (class "Default")
      (node (ref "R9") (pin "2") (pinfunction "2_2") (pintype "passive"))
      (node (ref "U4") (pin "31") (pinfunction "PD1(TXD)_31") (pintype "bidirectional"))
    )
    (net (code "72") (name "USBVCC") (class "Default")
      (node (ref "C12") (pin "1") (pinfunction "P$1_1") (pintype "passive"))
      (node (ref "C13") (pin "1") (pinfunction "P$1_1") (pintype "passive"))
      (node (ref "F1") (pin "2") (pinfunction "2_2") (pintype "bidirectional"))
      (node (ref "Q1") (pin "3") (pinfunction "D_3") (pintype "bidirectional"))
      (node (ref "U1") (pin "15") (pinfunction "VCC_15") (pintype "bidirectional"))
    )
    (net (code "73") (name "unconnected-(IC4E-O-Pad12)") (class "Default")
      (node (ref "IC4") (pin "12") (pinfunction "O_12") (pintype "output"))
    )
    (net (code "74") (name "unconnected-(IC4F-O-Pad15)") (class "Default")
      (node (ref "IC4") (pin "15") (pinfunction "O_15") (pintype "output"))
    )
    (net (code "75") (name "unconnected-(JP5-Pad2)") (class "Default")
      (node (ref "JP5") (pin "2") (pinfunction "2_2") (pintype "passive"))
    )
    (net (code "76") (name "unconnected-(JP5-Pad8)") (class "Default")
      (node (ref "JP5") (pin "8") (pinfunction "8_8") (pintype "passive"))
    )
    (net (code "77") (name "unconnected-(JP12-PadID)") (class "Default")
      (node (ref "JP12") (pin "ID") (pinfunction "ID_ID") (pintype "bidirectional"))
    )
    (net (code "78") (name "unconnected-(U1-CBUS0-Pad18)") (class "Default")
      (node (ref "U1") (pin "18") (pinfunction "CBUS0_18") (pintype "bidirectional"))
    )
    (net (code "79") (name "unconnected-(U1-CBUS3-Pad19)") (class "Default")
      (node (ref "U1") (pin "19") (pinfunction "CBUS3_19") (pintype "bidirectional"))
    )
    (net (code "80") (name "unconnected-(U1-~{CTS}-Pad9)") (class "Default")
      (node (ref "U1") (pin "9") (pinfunction "~{CTS}_9") (pintype "bidirectional"))
    )
    (net (code "81") (name "unconnected-(U1-~{DCD}-Pad8)") (class "Default")
      (node (ref "U1") (pin "8") (pinfunction "~{DCD}_8") (pintype "bidirectional"))
    )
    (net (code "82") (name "unconnected-(U1-~{DSR}-Pad7)") (class "Default")
      (node (ref "U1") (pin "7") (pinfunction "~{DSR}_7") (pintype "bidirectional"))
    )
    (net (code "83") (name "unconnected-(U1-~{RI}-Pad5)") (class "Default")
      (node (ref "U1") (pin "5") (pinfunction "~{RI}_5") (pintype "bidirectional"))
    )
    (net (code "84") (name "unconnected-(U1-~{RTS}-Pad2)") (class "Default")
      (node (ref "U1") (pin "2") (pinfunction "~{RTS}_2") (pintype "bidirectional"))
    )
    (net (code "85") (name "unconnected-(U2-BP-Pad4)") (class "Default")
      (node (ref "U2") (pin "4") (pinfunction "BP_4") (pintype "input"))
    )
    (net (code "86") (name "unconnected-(U3-QH*-Pad9)") (class "Default")
      (node (ref "U3") (pin "9") (pinfunction "QH*_9") (pintype "tri_state"))
    )
    (net (code "87") (name "unconnected-(U4-ADC6-Pad19)") (class "Default")
      (node (ref "U4") (pin "19") (pinfunction "ADC6_19") (pintype "bidirectional"))
    )
    (net (code "88") (name "unconnected-(U4-ADC7-Pad22)") (class "Default")
      (node (ref "U4") (pin "22") (pinfunction "ADC7_22") (pintype "bidirectional"))
    )
    (net (code "89") (name "unconnected-(U4-AREF-Pad20)") (class "Default")
      (node (ref "U4") (pin "20") (pinfunction "AREF_20") (pintype "bidirectional"))
    )
    (net (code "90") (name "unconnected-(U4-PC3(ADC3)-Pad26)") (class "Default")
      (node (ref "U4") (pin "26") (pinfunction "PC3(ADC3)_26") (pintype "bidirectional"))
    )
    (net (code "91") (name "unconnected-(U4-PC4(ADC4{slash}SDA)-Pad27)") (class "Default")
      (node (ref "U4") (pin "27") (pinfunction "PC4(ADC4/SDA)_27") (pintype "bidirectional"))
    )
    (net (code "92") (name "unconnected-(U4-PC5(ADC5{slash}SCL)-Pad28)") (class "Default")
      (node (ref "U4") (pin "28") (pinfunction "PC5(ADC5/SCL)_28") (pintype "bidirectional"))
    )
    (net (code "93") (name "unconnected-(VREG-OUT-Pad2)") (class "Default")
      (node (ref "VREG") (pin "2") (pinfunction "OUT_2") (pintype "output"))
    )
    (net (code "94") (name "unconnected-(X1-CARD_DETECT1-PadCD2)") (class "Default")
      (node (ref "X1") (pin "CD2") (pinfunction "CARD_DETECT1_CD2") (pintype "passive"))
    )
    (net (code "95") (name "unconnected-(X1-DAT1-Pad8)") (class "Default")
      (node (ref "X1") (pin "8") (pinfunction "DAT1_8") (pintype "bidirectional"))
    )
    (net (code "96") (name "unconnected-(X1-DAT2-Pad1)") (class "Default")
      (node (ref "X1") (pin "1") (pinfunction "DAT2_1") (pintype "bidirectional"))
    )
  )
)
